# plata_nizhn.net
KiCad netlist of a schematic drawn in Altium Designer
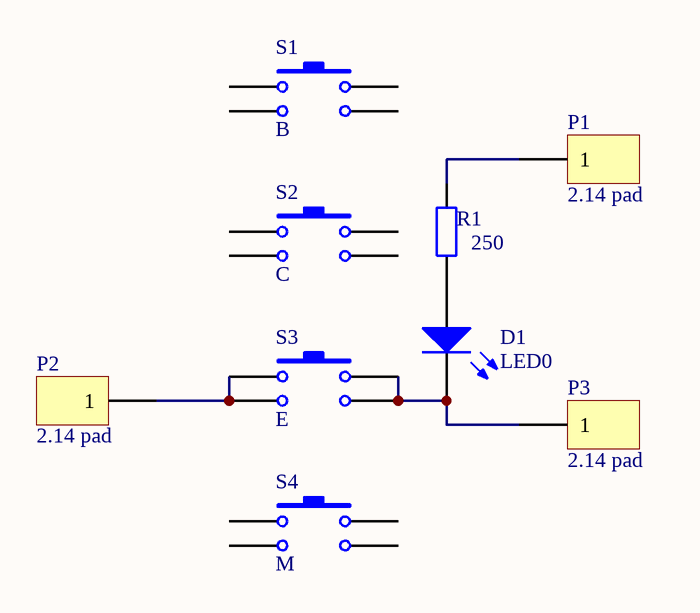
[diagram p0: plata_nizhn.SchDoc]

(export (version "E")
  (design (tool "Eeschema 10.0.6"))
  (components
    (comp (ref "D1")
      (value "LED0")
      (footprint "LED0805")
      (description "Typical INFRARED GaAs LED")
      (fields (field (name "PUBLISHER") "Altium Limited"))
      (libsource (lib "Library") (part "LED0"))
    )
    (comp (ref "P1")
      (value "2.14 pad")
      (footprint "Pad")
      (description "pad")
      (fields (field (name "PUBLISHER") "Altium Limited"))
      (libsource (lib "Library") (part "2.14 pad"))
    )
    (comp (ref "P2")
      (value "2.14 pad")
      (footprint "Pad")
      (description "pad")
      (fields (field (name "PUBLISHER") "Altium Limited"))
      (libsource (lib "") (part "2.14 pad_1"))
    )
    (comp (ref "P3")
      (value "2.14 pad")
      (footprint "Pad")
      (description "pad")
      (fields (field (name "PUBLISHER") "Altium Limited"))
      (libsource (lib "Library") (part "2.14 pad"))
    )
    (comp (ref "R1")
      (value "250")
      (footprint "6-0805_N")
      (description "Resistor")
      (fields (field (name "PUBLISHER") "Altium Limited"))
      (libsource (lib "Library") (part "Res2"))
    )
    (comp (ref "S1")
      (value "B")
      (footprint "STMW")
      (description "Switch")
      (fields (field (name "PUBLISHER") "Altium Limited"))
      (libsource (lib "Library") (part "STMW"))
    )
    (comp (ref "S2")
      (value "C")
      (footprint "STMW")
      (description "Switch")
      (fields (field (name "PUBLISHER") "Altium Limited"))
      (libsource (lib "Library") (part "STMW"))
    )
    (comp (ref "S3")
      (value "E")
      (footprint "STMW")
      (description "Switch")
      (fields (field (name "PUBLISHER") "Altium Limited"))
      (libsource (lib "Library") (part "STMW"))
    )
    (comp (ref "S4")
      (value "M")
      (footprint "STMW")
      (description "Switch")
      (fields (field (name "PUBLISHER") "Altium Limited"))
      (libsource (lib "Library") (part "STMW"))
    )
  )
  (nets
    (net (code "1") (name "Net-(D1-A)") (class "Default")
      (node (ref "D1") (pin "1") (pinfunction "A_1") (pintype "passive"))
      (node (ref "R1") (pin "1") (pinfunction "1_1") (pintype "passive"))
    )
    (net (code "2") (name "Net-(D1-K)") (class "Default")
      (node (ref "D1") (pin "2") (pinfunction "K_2") (pintype "passive"))
      (node (ref "P3") (pin "1") (pinfunction "1_1") (pintype "passive"))
      (node (ref "S3") (pin "2") (pinfunction "2_2") (pintype "passive"))
    )
    (net (code "3") (name "Net-(P1-Pad1)") (class "Default")
      (node (ref "P1") (pin "1") (pinfunction "1_1") (pintype "passive"))
      (node (ref "R1") (pin "2") (pinfunction "2_2") (pintype "passive"))
    )
    (net (code "4") (name "Net-(P2-Pad1)") (class "Default")
      (node (ref "P2") (pin "1") (pinfunction "1_1") (pintype "passive"))
      (node (ref "S3") (pin "1") (pinfunction "1_1") (pintype "passive"))
    )
    (net (code "5") (name "unconnected-(S1-Pad1)") (class "Default")
      (node (ref "S1") (pin "1") (pinfunction "1_1") (pintype "passive"))
    )
    (net (code "6") (name "unconnected-(S1-Pad1)_1") (class "Default")
      (node (ref "S1") (pin "1") (pinfunction "1_1") (pintype "passive"))
    )
    (net (code "7") (name "unconnected-(S1-Pad2)") (class "Default")
      (node (ref "S1") (pin "2") (pinfunction "2_2") (pintype "passive"))
    )
    (net (code "8") (name "unconnected-(S1-Pad2)_1") (class "Default")
      (node (ref "S1") (pin "2") (pinfunction "2_2") (pintype "passive"))
    )
    (net (code "9") (name "unconnected-(S2-Pad1)") (class "Default")
      (node (ref "S2") (pin "1") (pinfunction "1_1") (pintype "passive"))
    )
    (net (code "10") (name "unconnected-(S2-Pad1)_1") (class "Default")
      (node (ref "S2") (pin "1") (pinfunction "1_1") (pintype "passive"))
    )
    (net (code "11") (name "unconnected-(S2-Pad2)") (class "Default")
      (node (ref "S2") (pin "2") (pinfunction "2_2") (pintype "passive"))
    )
    (net (code "12") (name "unconnected-(S2-Pad2)_1") (class "Default")
      (node (ref "S2") (pin "2") (pinfunction "2_2") (pintype "passive"))
    )
    (net (code "13") (name "unconnected-(S4-Pad1)") (class "Default")
      (node (ref "S4") (pin "1") (pinfunction "1_1") (pintype "passive"))
    )
    (net (code "14") (name "unconnected-(S4-Pad1)_1") (class "Default")
      (node (ref "S4") (pin "1") (pinfunction "1_1") (pintype "passive"))
    )
    (net (code "15") (name "unconnected-(S4-Pad2)") (class "Default")
      (node (ref "S4") (pin "2") (pinfunction "2_2") (pintype "passive"))
    )
    (net (code "16") (name "unconnected-(S4-Pad2)_1") (class "Default")
      (node (ref "S4") (pin "2") (pinfunction "2_2") (pintype "passive"))
    )
  )
)
